# 32_-.net
KiCad netlist of a schematic drawn in Altium Designer
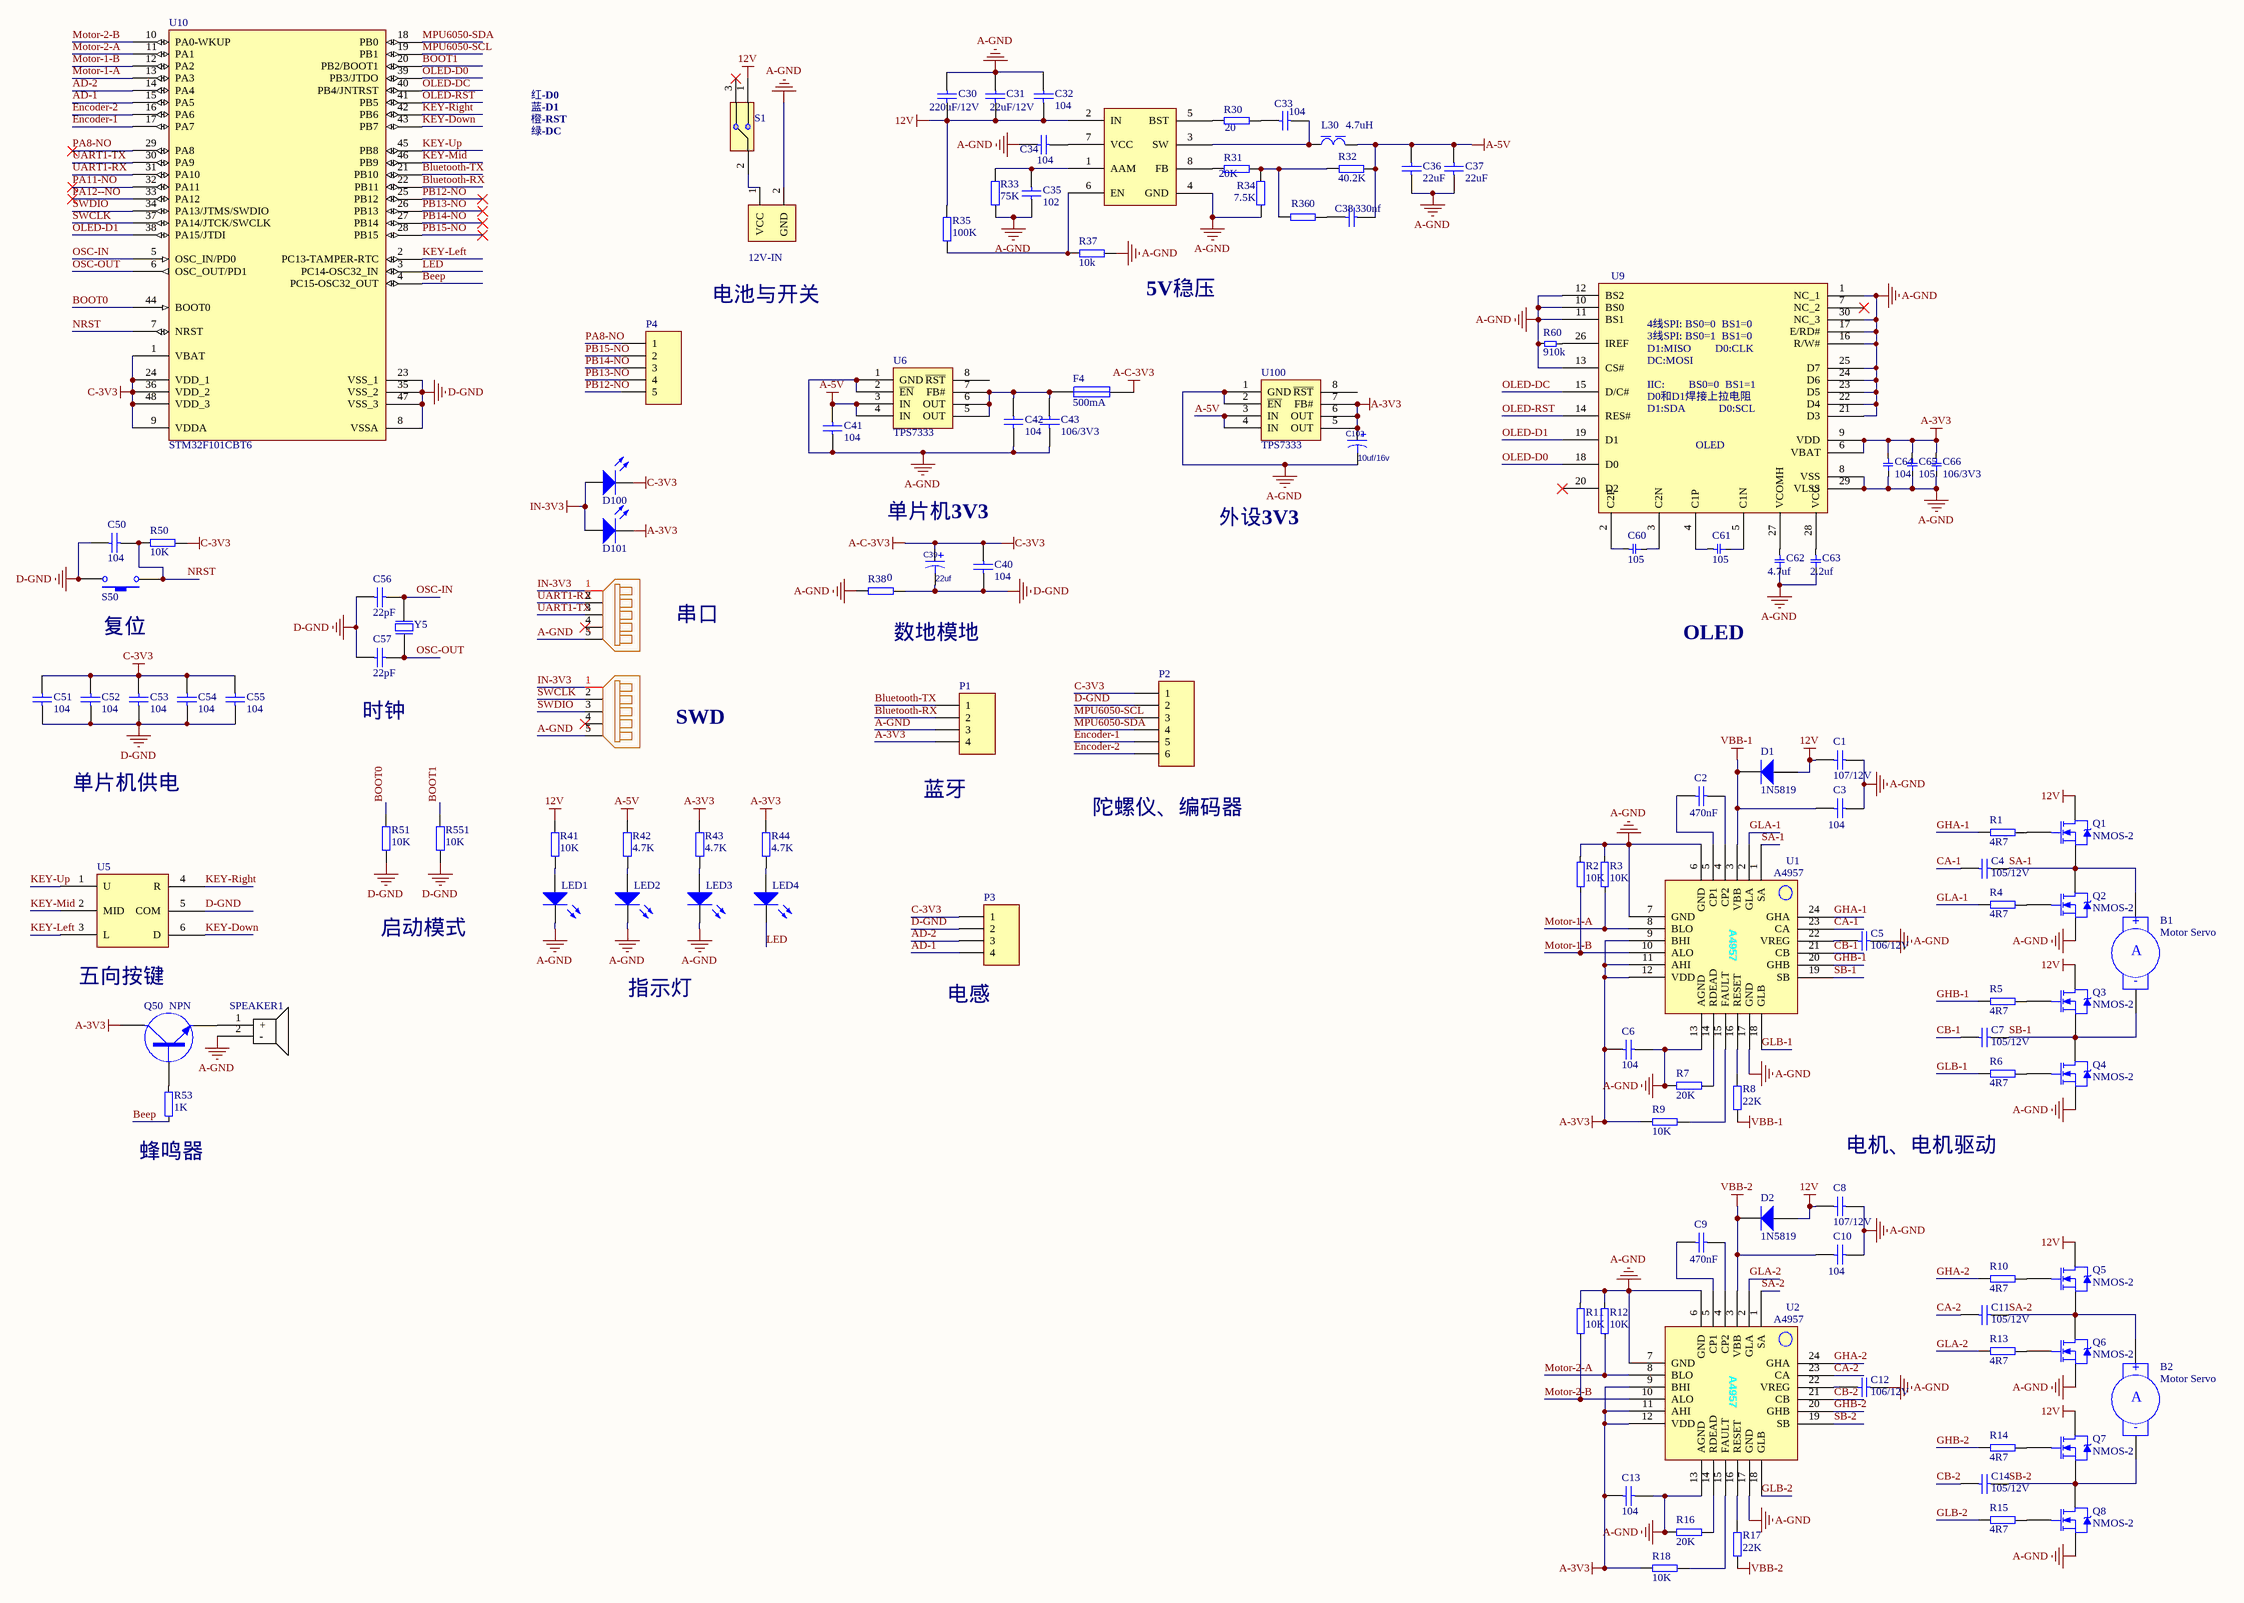
[diagram p0: 32直立车-原理图.SchDoc]

(export (version "E")
  (design (tool "Eeschema 10.0.6"))
  (components
    (comp (ref "12V-IN") (value "Power12") (footprint "VBAT-2") (libsource (lib "电磁第一版") (part "Power12")))
    (comp (ref "B1")
      (value "Motor Servo")
      (footprint "电机接口 - duplicate")
      (description "Servo Motor")
      (fields (field (name "PUBLISHER") "Altium Limited"))
      (libsource (lib "Miscellaneous Devices") (part "Motor Servo"))
    )
    (comp (ref "B2")
      (value "Motor Servo")
      (footprint "电机接口 - duplicate")
      (description "Servo Motor")
      (fields (field (name "PUBLISHER") "Altium Limited"))
      (libsource (lib "Miscellaneous Devices") (part "Motor Servo"))
    )
    (comp (ref "C1")
      (value "107/12V")
      (footprint "CAPC4532[1812]")
      (description "Chip Capacitor, Silkscreen Border")
      (fields
        (field (name "VOLTAGE") "63V")
        (field (name "TOLERANCE") "Y5V")
        (field (name "PUBLISHER") "Altium Limited")
      )
      (libsource (lib "!)Miscellaneous Integrated Library") (part "Cap Chip 2"))
    )
    (comp (ref "C2")
      (value "470nF")
      (footprint "CAPC1608[0603]")
      (description "Chip Capacitor, Silkscreen Border")
      (fields
        (field (name "VOLTAGE") "63V")
        (field (name "TOLERANCE") "Y5V")
        (field (name "PUBLISHER") "Altium Limited")
      )
      (libsource (lib "!)Miscellaneous Integrated Library") (part "Cap Chip 2"))
    )
    (comp (ref "C3")
      (value "104")
      (footprint "CAPC1608[0603]")
      (description "Chip Capacitor, Silkscreen Border")
      (fields
        (field (name "VOLTAGE") "63V")
        (field (name "TOLERANCE") "Y5V")
        (field (name "PUBLISHER") "Altium Limited")
      )
      (libsource (lib "!)Miscellaneous Integrated Library") (part "Cap Chip 2"))
    )
    (comp (ref "C4")
      (value "105/12V")
      (footprint "CAPC1608[0603]")
      (description "Chip Capacitor, Silkscreen Border")
      (fields
        (field (name "VOLTAGE") "63V")
        (field (name "TOLERANCE") "Y5V")
        (field (name "PUBLISHER") "Altium Limited")
      )
      (libsource (lib "!)Miscellaneous Integrated Library") (part "Cap Chip 2"))
    )
    (comp (ref "C5")
      (value "106/12V")
      (footprint "CAPC2012[0805]")
      (description "Chip Capacitor, Silkscreen Border")
      (fields
        (field (name "VOLTAGE") "63V")
        (field (name "TOLERANCE") "Y5V")
        (field (name "PUBLISHER") "Altium Limited")
      )
      (libsource (lib "!)Miscellaneous Integrated Library") (part "Cap Chip 2"))
    )
    (comp (ref "C6")
      (value "104")
      (footprint "CAPC1608[0603]")
      (description "Chip Capacitor, Silkscreen Border")
      (fields
        (field (name "VOLTAGE") "63V")
        (field (name "TOLERANCE") "Y5V")
        (field (name "PUBLISHER") "Altium Limited")
      )
      (libsource (lib "!)Miscellaneous Integrated Library") (part "Cap Chip 2"))
    )
    (comp (ref "C7")
      (value "105/12V")
      (footprint "CAPC1608[0603]")
      (description "Chip Capacitor, Silkscreen Border")
      (fields
        (field (name "VOLTAGE") "63V")
        (field (name "TOLERANCE") "Y5V")
        (field (name "PUBLISHER") "Altium Limited")
      )
      (libsource (lib "!)Miscellaneous Integrated Library") (part "Cap Chip 2"))
    )
    (comp (ref "C8")
      (value "107/12V")
      (footprint "CAPC4532[1812]")
      (description "Chip Capacitor, Silkscreen Border")
      (fields
        (field (name "VOLTAGE") "63V")
        (field (name "TOLERANCE") "Y5V")
        (field (name "PUBLISHER") "Altium Limited")
      )
      (libsource (lib "!)Miscellaneous Integrated Library") (part "Cap Chip 2"))
    )
    (comp (ref "C9")
      (value "470nF")
      (footprint "CAPC1608[0603]")
      (description "Chip Capacitor, Silkscreen Border")
      (fields
        (field (name "VOLTAGE") "63V")
        (field (name "TOLERANCE") "Y5V")
        (field (name "PUBLISHER") "Altium Limited")
      )
      (libsource (lib "!)Miscellaneous Integrated Library") (part "Cap Chip 2"))
    )
    (comp (ref "C10")
      (value "104")
      (footprint "CAPC1608[0603]")
      (description "Chip Capacitor, Silkscreen Border")
      (fields
        (field (name "VOLTAGE") "63V")
        (field (name "TOLERANCE") "Y5V")
        (field (name "PUBLISHER") "Altium Limited")
      )
      (libsource (lib "!)Miscellaneous Integrated Library") (part "Cap Chip 2"))
    )
    (comp (ref "C11")
      (value "105/12V")
      (footprint "CAPC1608[0603]")
      (description "Chip Capacitor, Silkscreen Border")
      (fields
        (field (name "VOLTAGE") "63V")
        (field (name "TOLERANCE") "Y5V")
        (field (name "PUBLISHER") "Altium Limited")
      )
      (libsource (lib "!)Miscellaneous Integrated Library") (part "Cap Chip 2"))
    )
    (comp (ref "C12")
      (value "106/12V")
      (footprint "CAPC2012[0805]")
      (description "Chip Capacitor, Silkscreen Border")
      (fields
        (field (name "VOLTAGE") "63V")
        (field (name "TOLERANCE") "Y5V")
        (field (name "PUBLISHER") "Altium Limited")
      )
      (libsource (lib "!)Miscellaneous Integrated Library") (part "Cap Chip 2"))
    )
    (comp (ref "C13")
      (value "104")
      (footprint "CAPC1608[0603]")
      (description "Chip Capacitor, Silkscreen Border")
      (fields
        (field (name "VOLTAGE") "63V")
        (field (name "TOLERANCE") "Y5V")
        (field (name "PUBLISHER") "Altium Limited")
      )
      (libsource (lib "!)Miscellaneous Integrated Library") (part "Cap Chip 2"))
    )
    (comp (ref "C14")
      (value "105/12V")
      (footprint "CAPC1608[0603]")
      (description "Chip Capacitor, Silkscreen Border")
      (fields
        (field (name "VOLTAGE") "63V")
        (field (name "TOLERANCE") "Y5V")
        (field (name "PUBLISHER") "Altium Limited")
      )
      (libsource (lib "!)Miscellaneous Integrated Library") (part "Cap Chip 2"))
    )
    (comp (ref "C30")
      (value "220uF/12V")
      (footprint "CAPT7343")
      (description "Chip Capacitor, PSpice Model")
      (fields (field (name "TOLERANCE") "Y5V") (field (name "PUBLISHER") "Altium Limited"))
      (libsource (lib "!)Miscellaneous Integrated Library") (part "Cap Chip 1"))
    )
    (comp (ref "C31")
      (value "22uF/12V")
      (footprint "CAPC2012[0805]")
      (description "Chip Capacitor, PSpice Model")
      (fields
        (field (name "TOLERANCE") "Y5V")
        (field (name "VOLTAGE") "63V")
        (field (name "PUBLISHER") "Altium Limited")
      )
      (libsource (lib "!)Miscellaneous Integrated Library") (part "Cap Chip 1"))
    )
    (comp (ref "C32")
      (value "104")
      (footprint "CAPC1608[0603]")
      (description "Chip Capacitor, PSpice Model")
      (fields
        (field (name "TOLERANCE") "Y5V")
        (field (name "VOLTAGE") "63V")
        (field (name "PUBLISHER") "Altium Limited")
      )
      (libsource (lib "!)Miscellaneous Integrated Library") (part "Cap Chip 1"))
    )
    (comp (ref "C33")
      (value "104")
      (footprint "CAPC1608[0603]")
      (description "Chip Capacitor, PSpice Model")
      (fields
        (field (name "TOLERANCE") "Y5V")
        (field (name "VOLTAGE") "63V")
        (field (name "PUBLISHER") "Altium Limited")
      )
      (libsource (lib "!)Miscellaneous Integrated Library") (part "Cap Chip 1"))
    )
    (comp (ref "C34")
      (value "104")
      (footprint "CAPC1608[0603]")
      (description "Chip Capacitor, PSpice Model")
      (fields
        (field (name "TOLERANCE") "Y5V")
        (field (name "VOLTAGE") "63V")
        (field (name "PUBLISHER") "Altium Limited")
      )
      (libsource (lib "!)Miscellaneous Integrated Library") (part "Cap Chip 1"))
    )
    (comp (ref "C35")
      (value "102")
      (footprint "CAPC1608[0603]")
      (description "Chip Capacitor, PSpice Model")
      (fields
        (field (name "TOLERANCE") "Y5V")
        (field (name "VOLTAGE") "63V")
        (field (name "PUBLISHER") "Altium Limited")
      )
      (libsource (lib "!)Miscellaneous Integrated Library") (part "Cap Chip 1"))
    )
    (comp (ref "C36")
      (value "22uF")
      (footprint "CAPC2012[0805]")
      (description "Chip Capacitor, PSpice Model")
      (fields
        (field (name "TOLERANCE") "Y5V")
        (field (name "VOLTAGE") "63V")
        (field (name "PUBLISHER") "Altium Limited")
      )
      (libsource (lib "!)Miscellaneous Integrated Library") (part "Cap Chip 1"))
    )
    (comp (ref "C37")
      (value "22uF")
      (footprint "CAPC2012[0805]")
      (description "Chip Capacitor, PSpice Model")
      (fields
        (field (name "TOLERANCE") "Y5V")
        (field (name "VOLTAGE") "63V")
        (field (name "PUBLISHER") "Altium Limited")
      )
      (libsource (lib "!)Miscellaneous Integrated Library") (part "Cap Chip 1"))
    )
    (comp (ref "C38")
      (value "330nf")
      (footprint "CAPC1608[0603]")
      (description "Chip Capacitor, PSpice Model")
      (fields
        (field (name "TOLERANCE") "Y5V")
        (field (name "VOLTAGE") "63V")
        (field (name "PUBLISHER") "Altium Limited")
      )
      (libsource (lib "!)Miscellaneous Integrated Library") (part "Cap Chip 1"))
    )
    (comp (ref "C39")
      (value "22uf")
      (footprint "CAPT7343")
      (description "Polarized Capacitor (Axial)")
      (fields (field (name "Comment") "Cap Pol2") (field (name "PUBLISHER") "Altium Limited"))
      (libsource (lib "TheCar") (part "Cap Pol2"))
    )
    (comp (ref "C40")
      (value "104")
      (footprint "CAPC1608[0603]")
      (description "Chip Capacitor, PSpice Model")
      (fields
        (field (name "TOLERANCE") "Y5V")
        (field (name "VOLTAGE") "63V")
        (field (name "PUBLISHER") "Altium Limited")
      )
      (libsource (lib "!)Miscellaneous Integrated Library") (part "Cap Chip 1"))
    )
    (comp (ref "C41")
      (value "104")
      (footprint "CAPC1608[0603]")
      (description "Chip Capacitor, Silkscreen Border")
      (fields
        (field (name "VOLTAGE") "63V")
        (field (name "TOLERANCE") "Y5V")
        (field (name "PUBLISHER") "Altium Limited")
      )
      (libsource (lib "!)Miscellaneous Integrated Library") (part "Cap Chip 2"))
    )
    (comp (ref "C42")
      (value "104")
      (footprint "CAPC1608[0603]")
      (description "Chip Capacitor, Silkscreen Border")
      (fields
        (field (name "VOLTAGE") "63V")
        (field (name "TOLERANCE") "Y5V")
        (field (name "PUBLISHER") "Altium Limited")
      )
      (libsource (lib "!)Miscellaneous Integrated Library") (part "Cap Chip 2"))
    )
    (comp (ref "C43")
      (value "106/3V3")
      (footprint "CAPC1608[0603]")
      (description "Chip Capacitor, Silkscreen Border")
      (fields
        (field (name "VOLTAGE") "63V")
        (field (name "TOLERANCE") "Y5V")
        (field (name "PUBLISHER") "Altium Limited")
      )
      (libsource (lib "!)Miscellaneous Integrated Library") (part "Cap Chip 2"))
    )
    (comp (ref "C50")
      (value "104")
      (footprint "CAPC1608[0603]")
      (description "Chip Capacitor, Silkscreen Border")
      (fields
        (field (name "VOLTAGE") "63V")
        (field (name "TOLERANCE") "Y5V")
        (field (name "PUBLISHER") "Altium Limited")
      )
      (libsource (lib "!)Miscellaneous Integrated Library") (part "Cap Chip 2"))
    )
    (comp (ref "C51")
      (value "104")
      (footprint "CAPC1608[0603]")
      (description "Chip Capacitor, Silkscreen Border")
      (fields
        (field (name "VOLTAGE") "63V")
        (field (name "TOLERANCE") "Y5V")
        (field (name "PUBLISHER") "Altium Limited")
      )
      (libsource (lib "!)Miscellaneous Integrated Library") (part "Cap Chip 2"))
    )
    (comp (ref "C52")
      (value "104")
      (footprint "CAPC1608[0603]")
      (description "Chip Capacitor, Silkscreen Border")
      (fields
        (field (name "VOLTAGE") "63V")
        (field (name "TOLERANCE") "Y5V")
        (field (name "PUBLISHER") "Altium Limited")
      )
      (libsource (lib "!)Miscellaneous Integrated Library") (part "Cap Chip 2"))
    )
    (comp (ref "C53")
      (value "104")
      (footprint "CAPC1608[0603]")
      (description "Chip Capacitor, Silkscreen Border")
      (fields
        (field (name "VOLTAGE") "63V")
        (field (name "TOLERANCE") "Y5V")
        (field (name "PUBLISHER") "Altium Limited")
      )
      (libsource (lib "!)Miscellaneous Integrated Library") (part "Cap Chip 2"))
    )
    (comp (ref "C54")
      (value "104")
      (footprint "CAPC1608[0603]")
      (description "Chip Capacitor, Silkscreen Border")
      (fields
        (field (name "VOLTAGE") "63V")
        (field (name "TOLERANCE") "Y5V")
        (field (name "PUBLISHER") "Altium Limited")
      )
      (libsource (lib "!)Miscellaneous Integrated Library") (part "Cap Chip 2"))
    )
    (comp (ref "C55")
      (value "104")
      (footprint "CAPC1608[0603]")
      (description "Chip Capacitor, Silkscreen Border")
      (fields
        (field (name "VOLTAGE") "63V")
        (field (name "TOLERANCE") "Y5V")
        (field (name "PUBLISHER") "Altium Limited")
      )
      (libsource (lib "!)Miscellaneous Integrated Library") (part "Cap Chip 2"))
    )
    (comp (ref "C56")
      (value "22pF")
      (footprint "CAPC1608[0603]")
      (description "Chip Capacitor, Silkscreen Border")
      (fields
        (field (name "VOLTAGE") "63V")
        (field (name "TOLERANCE") "Y5V")
        (field (name "PUBLISHER") "Altium Limited")
      )
      (libsource (lib "!)Miscellaneous Integrated Library") (part "Cap Chip 2"))
    )
    (comp (ref "C57")
      (value "22pF")
      (footprint "CAPC1608[0603]")
      (description "Chip Capacitor, Silkscreen Border")
      (fields
        (field (name "VOLTAGE") "63V")
        (field (name "TOLERANCE") "Y5V")
        (field (name "PUBLISHER") "Altium Limited")
      )
      (libsource (lib "!)Miscellaneous Integrated Library") (part "Cap Chip 2"))
    )
    (comp (ref "C60") (value "105") (footprint "CAPC1608[0603]") (libsource (lib "电容") (part "ECAP")))
    (comp (ref "C61") (value "105") (footprint "CAPC1608[0603]") (libsource (lib "电容") (part "ECAP")))
    (comp (ref "C62") (value "4.7uf") (footprint "CAPC2012[0805]") (libsource (lib "电容") (part "ECAP")))
    (comp (ref "C63") (value "2.2uf") (footprint "CAPC1608[0603]") (libsource (lib "电容") (part "ECAP")))
    (comp (ref "C64") (value "104") (footprint "CAPC1608[0603]") (libsource (lib "电容") (part "ECAP")))
    (comp (ref "C65") (value "105") (footprint "CAPC1608[0603]") (libsource (lib "电容") (part "ECAP")))
    (comp (ref "C66") (value "106/3V3") (footprint "CAPC2012[0805]") (libsource (lib "电容") (part "ECAP")))
    (comp (ref "C102")
      (value "10uf/16v")
      (footprint "钽电容3216")
      (description "Polarized Capacitor (Axial)")
      (fields (field (name "Comment") "Cap Pol2") (field (name "PUBLISHER") "Altium Limited"))
      (libsource (lib "TheCar") (part "Cap Pol2"))
    )
    (comp (ref "D1")
      (value "1N5819")
      (footprint "SMA[DO-214AC]")
      (description "Default Diode")
      (fields (field (name "PUBLISHER") "Altium Limited"))
      (libsource (lib "Miscellaneous Devices") (part "Diode"))
    )
    (comp (ref "D2")
      (value "1N5819")
      (footprint "SMA[DO-214AC]")
      (description "Default Diode")
      (fields (field (name "PUBLISHER") "Altium Limited"))
      (libsource (lib "Miscellaneous Devices") (part "Diode"))
    )
    (comp (ref "D100")
      (value "Red")
      (footprint "LED-0603")
      (description "Typical Chip LED")
      (fields (field (name "PUBLISHER") "Altium Limited"))
      (libsource (lib "!)Miscellaneous Integrated Library") (part "LED Chip"))
    )
    (comp (ref "D101")
      (value "Red")
      (footprint "LED-0603")
      (description "Typical Chip LED")
      (fields (field (name "PUBLISHER") "Altium Limited"))
      (libsource (lib "!)Miscellaneous Integrated Library") (part "LED Chip"))
    )
    (comp (ref "F4")
      (value "500mA")
      (footprint "CAPC2012[0805]")
      (description "Fuse")
      (fields (field (name "PUBLISHER") "Altium Limited"))
      (libsource (lib "主板 v2.0 最小系统") (part "Fuse chip"))
    )
    (comp (ref "L30")
      (value "4.7uH")
      (footprint "CD52")
      (description "Power Inductor, Ferrite-Core")
      (fields (field (name "PUBLISHER") "Altium Limited"))
      (libsource (lib "!)Miscellaneous Integrated Library") (part "Ind Power"))
    )
    (comp (ref "LED1")
      (value "Red")
      (footprint "LEDC1608(0603)")
      (description "Typical Chip LED")
      (fields (field (name "PUBLISHER") "Altium Limited"))
      (libsource (lib "") (part "LED Chip_1"))
    )
    (comp (ref "LED2")
      (value "Red")
      (footprint "LEDC1608(0603)")
      (description "Typical Chip LED")
      (fields (field (name "PUBLISHER") "Altium Limited"))
      (libsource (lib "") (part "LED Chip_1"))
    )
    (comp (ref "LED3")
      (value "Red")
      (footprint "LEDC1608(0603)")
      (description "Typical Chip LED")
      (fields (field (name "PUBLISHER") "Altium Limited"))
      (libsource (lib "") (part "LED Chip_1"))
    )
    (comp (ref "LED4")
      (value "Red")
      (footprint "LEDC1608(0603)")
      (description "Typical Chip LED")
      (fields (field (name "PUBLISHER") "Altium Limited"))
      (libsource (lib "") (part "LED Chip_1"))
    )
    (comp (ref "P1")
      (value "~")
      (footprint "MK1.25_4P立")
      (description "Header, 4-Pin")
      (fields (field (name "PUBLISHER") "Altium Limited"))
      (libsource (lib "!)Miscellaneous Integrated Library") (part "Header 4"))
    )
    (comp (ref "P2")
      (value "陀螺仪、编码器")
      (footprint "6P-卧头")
      (description "Header, 6-Pin")
      (fields (field (name "PUBLISHER") "Altium Limited"))
      (libsource (lib "!)Miscellaneous Integrated Library") (part "Header 6"))
    )
    (comp (ref "P3")
      (value "~")
      (footprint "MK1.25_4P立")
      (description "Header, 4-Pin")
      (fields (field (name "PUBLISHER") "Altium Limited"))
      (libsource (lib "!)Miscellaneous Integrated Library") (part "Header 4"))
    )
    (comp (ref "P4")
      (value "Header 5")
      (footprint "扩展口-5P")
      (description "Header, 5-Pin")
      (fields (field (name "PUBLISHER") "Altium Limited"))
      (libsource (lib "!)Miscellaneous Integrated Library") (part "Header 5"))
    )
    (comp (ref "Q1")
      (value "NMOS-2")
      (footprint "IR7843-mg")
      (description "N-Channel Power MOSFET")
      (fields (field (name "PUBLISHER") "Altium Limited"))
      (libsource (lib "Miscellaneous Devices") (part "NMOS-2"))
    )
    (comp (ref "Q2")
      (value "NMOS-2")
      (footprint "IR7843-mg")
      (description "N-Channel Power MOSFET")
      (fields (field (name "PUBLISHER") "Altium Limited"))
      (libsource (lib "Miscellaneous Devices") (part "NMOS-2"))
    )
    (comp (ref "Q3")
      (value "NMOS-2")
      (footprint "IR7843-mg")
      (description "N-Channel Power MOSFET")
      (fields (field (name "PUBLISHER") "Altium Limited"))
      (libsource (lib "Miscellaneous Devices") (part "NMOS-2"))
    )
    (comp (ref "Q4")
      (value "NMOS-2")
      (footprint "IR7843-mg")
      (description "N-Channel Power MOSFET")
      (fields (field (name "PUBLISHER") "Altium Limited"))
      (libsource (lib "Miscellaneous Devices") (part "NMOS-2"))
    )
    (comp (ref "Q5")
      (value "NMOS-2")
      (footprint "IR7843-mg")
      (description "N-Channel Power MOSFET")
      (fields (field (name "PUBLISHER") "Altium Limited"))
      (libsource (lib "Miscellaneous Devices") (part "NMOS-2"))
    )
    (comp (ref "Q6")
      (value "NMOS-2")
      (footprint "IR7843-mg")
      (description "N-Channel Power MOSFET")
      (fields (field (name "PUBLISHER") "Altium Limited"))
      (libsource (lib "Miscellaneous Devices") (part "NMOS-2"))
    )
    (comp (ref "Q7")
      (value "NMOS-2")
      (footprint "IR7843-mg")
      (description "N-Channel Power MOSFET")
      (fields (field (name "PUBLISHER") "Altium Limited"))
      (libsource (lib "Miscellaneous Devices") (part "NMOS-2"))
    )
    (comp (ref "Q8")
      (value "NMOS-2")
      (footprint "IR7843-mg")
      (description "N-Channel Power MOSFET")
      (fields (field (name "PUBLISHER") "Altium Limited"))
      (libsource (lib "Miscellaneous Devices") (part "NMOS-2"))
    )
    (comp (ref "Q50")
      (value "NPN")
      (footprint "SOT23")
      (description "NPN Transistor")
      (libsource (lib "杂元件库") (part "NPN"))
    )
    (comp (ref "R1")
      (value "4R7")
      (footprint "RESC1608[0603]")
      (description "Chip Resistor, Border Silkscreen On PCB Library")
      (fields (field (name "TOLERANCE") "5%") (field (name "PUBLISHER") "Altium Limited"))
      (libsource (lib "!)Miscellaneous Integrated Library") (part "Res Chip 2p 2"))
    )
    (comp (ref "R2")
      (value "10K")
      (footprint "RESC1608[0603]")
      (description "resistor")
      (libsource (lib "常用原理图.~(18)") (part "R-10K"))
    )
    (comp (ref "R3")
      (value "10K")
      (footprint "RESC1608[0603]")
      (description "resistor")
      (libsource (lib "常用原理图.~(18)") (part "R-10K"))
    )
    (comp (ref "R4")
      (value "4R7")
      (footprint "RESC1608[0603]")
      (description "Chip Resistor, Border Silkscreen On PCB Library")
      (fields (field (name "TOLERANCE") "5%") (field (name "PUBLISHER") "Altium Limited"))
      (libsource (lib "!)Miscellaneous Integrated Library") (part "Res Chip 2p 2"))
    )
    (comp (ref "R5")
      (value "4R7")
      (footprint "RESC1608[0603]")
      (description "Chip Resistor, Border Silkscreen On PCB Library")
      (fields (field (name "TOLERANCE") "5%") (field (name "PUBLISHER") "Altium Limited"))
      (libsource (lib "!)Miscellaneous Integrated Library") (part "Res Chip 2p 2"))
    )
    (comp (ref "R6")
      (value "4R7")
      (footprint "RESC1608[0603]")
      (description "Chip Resistor, Border Silkscreen On PCB Library")
      (fields (field (name "TOLERANCE") "5%") (field (name "PUBLISHER") "Altium Limited"))
      (libsource (lib "!)Miscellaneous Integrated Library") (part "Res Chip 2p 2"))
    )
    (comp (ref "R7")
      (value "20K")
      (footprint "RESC1608[0603]")
      (description "Chip Resistor, Border Silkscreen On PCB Library")
      (fields (field (name "TOLERANCE") "5%") (field (name "PUBLISHER") "Altium Limited"))
      (libsource (lib "!)Miscellaneous Integrated Library") (part "Res Chip 2p 2"))
    )
    (comp (ref "R8")
      (value "22K")
      (footprint "RESC1608[0603]")
      (description "Chip Resistor, Border Silkscreen On PCB Library")
      (fields (field (name "TOLERANCE") "5%") (field (name "PUBLISHER") "Altium Limited"))
      (libsource (lib "!)Miscellaneous Integrated Library") (part "Res Chip 2p 2"))
    )
    (comp (ref "R9")
      (value "10K")
      (footprint "RESC1608[0603]")
      (description "Chip Resistor, Border Silkscreen On PCB Library")
      (fields (field (name "TOLERANCE") "5%") (field (name "PUBLISHER") "Altium Limited"))
      (libsource (lib "!)Miscellaneous Integrated Library") (part "Res Chip 2p 2"))
    )
    (comp (ref "R10")
      (value "4R7")
      (footprint "RESC1608[0603]")
      (description "Chip Resistor, Border Silkscreen On PCB Library")
      (fields (field (name "TOLERANCE") "5%") (field (name "PUBLISHER") "Altium Limited"))
      (libsource (lib "!)Miscellaneous Integrated Library") (part "Res Chip 2p 2"))
    )
    (comp (ref "R11")
      (value "10K")
      (footprint "RESC1608[0603]")
      (description "resistor")
      (libsource (lib "常用原理图.~(18)") (part "R-10K"))
    )
    (comp (ref "R12")
      (value "10K")
      (footprint "RESC1608[0603]")
      (description "resistor")
      (libsource (lib "常用原理图.~(18)") (part "R-10K"))
    )
    (comp (ref "R13")
      (value "4R7")
      (footprint "RESC1608[0603]")
      (description "Chip Resistor, Border Silkscreen On PCB Library")
      (fields (field (name "TOLERANCE") "5%") (field (name "PUBLISHER") "Altium Limited"))
      (libsource (lib "!)Miscellaneous Integrated Library") (part "Res Chip 2p 2"))
    )
    (comp (ref "R14")
      (value "4R7")
      (footprint "RESC1608[0603]")
      (description "Chip Resistor, Border Silkscreen On PCB Library")
      (fields (field (name "TOLERANCE") "5%") (field (name "PUBLISHER") "Altium Limited"))
      (libsource (lib "!)Miscellaneous Integrated Library") (part "Res Chip 2p 2"))
    )
    (comp (ref "R15")
      (value "4R7")
      (footprint "RESC1608[0603]")
      (description "Chip Resistor, Border Silkscreen On PCB Library")
      (fields (field (name "TOLERANCE") "5%") (field (name "PUBLISHER") "Altium Limited"))
      (libsource (lib "!)Miscellaneous Integrated Library") (part "Res Chip 2p 2"))
    )
    (comp (ref "R16")
      (value "20K")
      (footprint "RESC1608[0603]")
      (description "Chip Resistor, Border Silkscreen On PCB Library")
      (fields (field (name "TOLERANCE") "5%") (field (name "PUBLISHER") "Altium Limited"))
      (libsource (lib "!)Miscellaneous Integrated Library") (part "Res Chip 2p 2"))
    )
    (comp (ref "R17")
      (value "22K")
      (footprint "RESC1608[0603]")
      (description "Chip Resistor, Border Silkscreen On PCB Library")
      (fields (field (name "TOLERANCE") "5%") (field (name "PUBLISHER") "Altium Limited"))
      (libsource (lib "!)Miscellaneous Integrated Library") (part "Res Chip 2p 2"))
    )
    (comp (ref "R18")
      (value "10K")
      (footprint "RESC1608[0603]")
      (description "Chip Resistor, Border Silkscreen On PCB Library")
      (fields (field (name "TOLERANCE") "5%") (field (name "PUBLISHER") "Altium Limited"))
      (libsource (lib "!)Miscellaneous Integrated Library") (part "Res Chip 2p 2"))
    )
    (comp (ref "R30")
      (value "20")
      (footprint "RESC1608[0603]")
      (description "Chip Resistor, PSpice Model, IPC PCB Library Drawing")
      (fields (field (name "TOLERANCE") "5%") (field (name "PUBLISHER") "Altium Limited"))
      (libsource (lib "!)Miscellaneous Integrated Library") (part "Res Chip 2p 1"))
    )
    (comp (ref "R31")
      (value "20K")
      (footprint "RESC1608[0603]")
      (description "Chip Resistor, PSpice Model, IPC PCB Library Drawing")
      (fields (field (name "TOLERANCE") "5%") (field (name "PUBLISHER") "Altium Limited"))
      (libsource (lib "!)Miscellaneous Integrated Library") (part "Res Chip 2p 1"))
    )
    (comp (ref "R32")
      (value "40.2K")
      (footprint "RESC1608[0603]")
      (description "Chip Resistor, PSpice Model, IPC PCB Library Drawing")
      (fields (field (name "TOLERANCE") "5%") (field (name "PUBLISHER") "Altium Limited"))
      (libsource (lib "!)Miscellaneous Integrated Library") (part "Res Chip 2p 1"))
    )
    (comp (ref "R33")
      (value "75K")
      (footprint "RESC1608[0603]")
      (description "Chip Resistor, PSpice Model, IPC PCB Library Drawing")
      (fields (field (name "TOLERANCE") "5%") (field (name "PUBLISHER") "Altium Limited"))
      (libsource (lib "!)Miscellaneous Integrated Library") (part "Res Chip 2p 1"))
    )
    (comp (ref "R34")
      (value "7.5K")
      (footprint "RESC1608[0603]")
      (description "Chip Resistor, PSpice Model, IPC PCB Library Drawing")
      (fields (field (name "TOLERANCE") "5%") (field (name "PUBLISHER") "Altium Limited"))
      (libsource (lib "!)Miscellaneous Integrated Library") (part "Res Chip 2p 1"))
    )
    (comp (ref "R35")
      (value "100K")
      (footprint "RESC1608[0603]")
      (description "Chip Resistor, PSpice Model, IPC PCB Library Drawing")
      (fields (field (name "TOLERANCE") "5%") (field (name "PUBLISHER") "Altium Limited"))
      (libsource (lib "!)Miscellaneous Integrated Library") (part "Res Chip 2p 1"))
    )
    (comp (ref "R36")
      (value "0")
      (footprint "RESC1608[0603]")
      (description "Chip Resistor, PSpice Model, IPC PCB Library Drawing")
      (fields (field (name "TOLERANCE") "5%") (field (name "PUBLISHER") "Altium Limited"))
      (libsource (lib "!)Miscellaneous Integrated Library") (part "Res Chip 2p 1"))
    )
    (comp (ref "R37")
      (value "10k")
      (footprint "RESC1608[0603]")
      (description "Chip Resistor, PSpice Model, IPC PCB Library Drawing")
      (fields (field (name "TOLERANCE") "5%") (field (name "PUBLISHER") "Altium Limited"))
      (libsource (lib "!)Miscellaneous Integrated Library") (part "Res Chip 2p 1"))
    )
    (comp (ref "R38")
      (value "0")
      (footprint "RESC1608[0603]")
      (description "Chip Resistor, PSpice Model, IPC PCB Library Drawing")
      (fields (field (name "TOLERANCE") "5%") (field (name "PUBLISHER") "Altium Limited"))
      (libsource (lib "!)Miscellaneous Integrated Library") (part "Res Chip 2p 1"))
    )
    (comp (ref "R41")
      (value "10K")
      (footprint "RESC1608[0603]")
      (description "Chip Resistor, PSpice Model, IPC PCB Library Drawing")
      (fields (field (name "TOLERANCE") "5%") (field (name "PUBLISHER") "Altium Limited"))
      (libsource (lib "!)Miscellaneous Integrated Library") (part "Res Chip 2p 1"))
    )
    (comp (ref "R42")
      (value "4.7K")
      (footprint "RESC1608[0603]")
      (description "Chip Resistor, PSpice Model, IPC PCB Library Drawing")
      (fields (field (name "TOLERANCE") "5%") (field (name "PUBLISHER") "Altium Limited"))
      (libsource (lib "!)Miscellaneous Integrated Library") (part "Res Chip 2p 1"))
    )
    (comp (ref "R43")
      (value "4.7K")
      (footprint "RESC1608[0603]")
      (description "Chip Resistor, PSpice Model, IPC PCB Library Drawing")
      (fields (field (name "TOLERANCE") "5%") (field (name "PUBLISHER") "Altium Limited"))
      (libsource (lib "!)Miscellaneous Integrated Library") (part "Res Chip 2p 1"))
    )
    (comp (ref "R44")
      (value "4.7K")
      (footprint "RESC1608[0603]")
      (description "Chip Resistor, PSpice Model, IPC PCB Library Drawing")
      (fields (field (name "TOLERANCE") "5%") (field (name "PUBLISHER") "Altium Limited"))
      (libsource (lib "!)Miscellaneous Integrated Library") (part "Res Chip 2p 1"))
    )
    (comp (ref "R50")
      (value "10K")
      (footprint "RESC1608[0603]")
      (description "Chip Resistor, PSpice Model, IPC PCB Library Drawing")
      (fields (field (name "TOLERANCE") "5%") (field (name "PUBLISHER") "Altium Limited"))
      (libsource (lib "!)Miscellaneous Integrated Library") (part "Res Chip 2p 1"))
    )
    (comp (ref "R51")
      (value "10K")
      (footprint "RESC1608[0603]")
      (description "Chip Resistor, PSpice Model, IPC PCB Library Drawing")
      (fields (field (name "TOLERANCE") "5%") (field (name "PUBLISHER") "Altium Limited"))
      (libsource (lib "!)Miscellaneous Integrated Library") (part "Res Chip 2p 1"))
    )
    (comp (ref "R53") (value "1K") (footprint "RESC1608[0603]") (libsource (lib "电阻") (part "RES")))
    (comp (ref "R60")
      (value "910k")
      (footprint "RESC1608[0603]")
      (description "CR85-102J")
      (libsource (lib "常用原理图") (part "1K"))
    )
    (comp (ref "R551")
      (value "10K")
      (footprint "RESC1608[0603]")
      (description "Chip Resistor, PSpice Model, IPC PCB Library Drawing")
      (fields (field (name "TOLERANCE") "5%") (field (name "PUBLISHER") "Altium Limited"))
      (libsource (lib "!)Miscellaneous Integrated Library") (part "Res Chip 2p 1"))
    )
    (comp (ref "S1") (value "switch") (footprint "2(-1)脚3A开关-立") (libsource (lib "电磁第一版") (part "switch")))
    (comp (ref "S50")
      (value "SW-PB")
      (footprint "key3*4*2")
      (description "Switch")
      (fields (field (name "PUBLISHER") "Altium Limited"))
      (libsource (lib "!)Miscellaneous Integrated Library") (part "SW-PB"))
    )
    (comp (ref "SPEAKER1") (value "有源蜂鸣器") (footprint "小Beep") (libsource (lib "蜂鸣器") (part "有源蜂鸣器")))
    (comp (ref "U1")
      (value "A4957")
      (footprint "QFN-24")
      (description "A4957SESTR-T")
      (libsource (lib "A4957 Dual Motor Driver V1.0") (part "A4957"))
    )
    (comp (ref "U2")
      (value "A4957")
      (footprint "QFN-24")
      (description "A4957SESTR-T")
      (libsource (lib "A4957 Dual Motor Driver V1.0") (part "A4957"))
    )
    (comp (ref "U5") (value "五向按键") (footprint "5向key-小") (libsource (lib "没有的器件原理图") (part "五向按键")))
    (comp (ref "U6") (value "TPS7333") (footprint "SOIC8") (libsource (lib "库") (part "TPS73xx")))
    (comp (ref "U9") (value "oled") (footprint "oled") (libsource (lib "电磁第一版") (part "OLED_1306")))
    (comp (ref "U10")
      (value "STM32F101CBT6")
      (footprint "LQFP48_N")
      (description "STM32 ARM-based 32-bit MCU with 128 Kbytes Flash, 48-pin LQFP, Industrial Temperature")
      (fields (field (name "PUBLISHER") "Altium Limited"))
      (libsource (lib "ST Microcontroller 32-Bit STM32") (part "STM32F101CBT6"))
    )
    (comp (ref "U30") (value "MP2315") (footprint "MP2315用SOP8") (libsource (lib "相关原理图封装") (part "MP2315")))
    (comp (ref "U100") (value "TPS7333") (footprint "SOIC8") (libsource (lib "库") (part "TPS73xx")))
    (comp (ref "USB1")
      (value "USB-5P")
      (footprint "Micro USB 牛角")
      (description "USB CONNECTOR")
      (libsource (lib "!)Miscellaneous Integrated Library") (part "USB-5P"))
    )
    (comp (ref "USB2")
      (value "USB-5P")
      (footprint "Micro USB 牛角")
      (description "USB CONNECTOR")
      (libsource (lib "!)Miscellaneous Integrated Library") (part "USB-5P"))
    )
    (comp (ref "Y5")
      (value "~")
      (footprint "4脚晶振-5032")
      (description "Crystal Oscillator")
      (fields (field (name "PUBLISHER") "Altium Limited"))
      (libsource (lib "!)Miscellaneous Integrated Library") (part "XTAL"))
    )
  )
  (nets
    (net (code "2") (name "/AD-1") (class "Default")
      (node (ref "P3") (pin "4") (pinfunction "4_4") (pintype "passive"))
      (node (ref "U10") (pin "15") (pinfunction "PA5_15") (pintype "bidirectional"))
    )
    (net (code "3") (name "/AD-2") (class "Default")
      (node (ref "P3") (pin "3") (pinfunction "3_3") (pintype "passive"))
      (node (ref "U10") (pin "14") (pinfunction "PA4_14") (pintype "bidirectional"))
    )
    (net (code "4") (name "/BOOT0") (class "Default")
      (node (ref "R51") (pin "2") (pinfunction "2_2") (pintype "passive"))
      (node (ref "U10") (pin "44") (pinfunction "BOOT0_44") (pintype "input"))
    )
    (net (code "5") (name "/BOOT1") (class "Default")
      (node (ref "R551") (pin "2") (pinfunction "2_2") (pintype "passive"))
      (node (ref "U10") (pin "20") (pinfunction "PB2/BOOT1_20") (pintype "bidirectional"))
    )
    (net (code "6") (name "/Beep") (class "Default")
      (node (ref "R53") (pin "1") (pinfunction "1_1") (pintype "passive"))
      (node (ref "U10") (pin "4") (pinfunction "PC15-OSC32_OUT_4") (pintype "bidirectional"))
    )
    (net (code "7") (name "/Bluetooth-RX") (class "Default")
      (node (ref "P1") (pin "2") (pinfunction "2_2") (pintype "passive"))
      (node (ref "U10") (pin "22") (pinfunction "PB11_22") (pintype "bidirectional"))
    )
    (net (code "8") (name "/Bluetooth-TX") (class "Default")
      (node (ref "P1") (pin "1") (pinfunction "1_1") (pintype "passive"))
      (node (ref "U10") (pin "21") (pinfunction "PB10_21") (pintype "bidirectional"))
    )
    (net (code "9") (name "/CA-1") (class "Default")
      (node (ref "C4") (pin "1") (pinfunction "1_1") (pintype "passive"))
      (node (ref "U1") (pin "23") (pinfunction "CA_23") (pintype "passive"))
    )
    (net (code "10") (name "/CA-2") (class "Default")
      (node (ref "C11") (pin "1") (pinfunction "1_1") (pintype "passive"))
      (node (ref "U2") (pin "23") (pinfunction "CA_23") (pintype "passive"))
    )
    (net (code "11") (name "/CB-1") (class "Default")
      (node (ref "C7") (pin "1") (pinfunction "1_1") (pintype "passive"))
      (node (ref "U1") (pin "21") (pinfunction "CB_21") (pintype "passive"))
    )
    (net (code "12") (name "/CB-2") (class "Default")
      (node (ref "C14") (pin "1") (pinfunction "1_1") (pintype "passive"))
      (node (ref "U2") (pin "21") (pinfunction "CB_21") (pintype "passive"))
    )
    (net (code "13") (name "/Encoder-1") (class "Default")
      (node (ref "P2") (pin "5") (pinfunction "5_5") (pintype "passive"))
      (node (ref "U10") (pin "17") (pinfunction "PA7_17") (pintype "bidirectional"))
    )
    (net (code "14") (name "/Encoder-2") (class "Default")
      (node (ref "P2") (pin "6") (pinfunction "6_6") (pintype "passive"))
      (node (ref "U10") (pin "16") (pinfunction "PA6_16") (pintype "bidirectional"))
    )
    (net (code "15") (name "/GHA-1") (class "Default")
      (node (ref "R1") (pin "2") (pinfunction "2_2") (pintype "passive"))
      (node (ref "U1") (pin "24") (pinfunction "GHA_24") (pintype "passive"))
    )
    (net (code "16") (name "/GHA-2") (class "Default")
      (node (ref "R10") (pin "2") (pinfunction "2_2") (pintype "passive"))
      (node (ref "U2") (pin "24") (pinfunction "GHA_24") (pintype "passive"))
    )
    (net (code "17") (name "/GHB-1") (class "Default")
      (node (ref "R5") (pin "2") (pinfunction "2_2") (pintype "passive"))
      (node (ref "U1") (pin "20") (pinfunction "GHB_20") (pintype "passive"))
    )
    (net (code "18") (name "/GHB-2") (class "Default")
      (node (ref "R14") (pin "2") (pinfunction "2_2") (pintype "passive"))
      (node (ref "U2") (pin "20") (pinfunction "GHB_20") (pintype "passive"))
    )
    (net (code "19") (name "/GLA-1") (class "Default")
      (node (ref "R4") (pin "1") (pinfunction "1_1") (pintype "passive"))
      (node (ref "U1") (pin "2") (pinfunction "GLA_2") (pintype "passive"))
    )
    (net (code "20") (name "/GLA-2") (class "Default")
      (node (ref "R13") (pin "1") (pinfunction "1_1") (pintype "passive"))
      (node (ref "U2") (pin "2") (pinfunction "GLA_2") (pintype "passive"))
    )
    (net (code "21") (name "/GLB-1") (class "Default")
      (node (ref "R6") (pin "1") (pinfunction "1_1") (pintype "passive"))
      (node (ref "U1") (pin "18") (pinfunction "GLB_18") (pintype "passive"))
    )
    (net (code "22") (name "/GLB-2") (class "Default")
      (node (ref "R15") (pin "1") (pinfunction "1_1") (pintype "passive"))
      (node (ref "U2") (pin "18") (pinfunction "GLB_18") (pintype "passive"))
    )
    (net (code "23") (name "/KEY-Down") (class "Default")
      (node (ref "U10") (pin "43") (pinfunction "PB7_43") (pintype "bidirectional"))
      (node (ref "U5") (pin "6") (pinfunction "D_6") (pintype "passive"))
    )
    (net (code "24") (name "/KEY-Left") (class "Default")
      (node (ref "U10") (pin "2") (pinfunction "PC13-TAMPER-RTC_2") (pintype "bidirectional"))
      (node (ref "U5") (pin "3") (pinfunction "L_3") (pintype "passive"))
    )
    (net (code "25") (name "/KEY-Mid") (class "Default")
      (node (ref "U10") (pin "46") (pinfunction "PB9_46") (pintype "bidirectional"))
      (node (ref "U5") (pin "2") (pinfunction "MID_2") (pintype "passive"))
    )
    (net (code "26") (name "/KEY-Right") (class "Default")
      (node (ref "U10") (pin "42") (pinfunction "PB6_42") (pintype "bidirectional"))
      (node (ref "U5") (pin "4") (pinfunction "R_4") (pintype "passive"))
    )
    (net (code "27") (name "/KEY-Up") (class "Default")
      (node (ref "U10") (pin "45") (pinfunction "PB8_45") (pintype "bidirectional"))
      (node (ref "U5") (pin "1") (pinfunction "U_1") (pintype "passive"))
    )
    (net (code "28") (name "/LED") (class "Default")
      (node (ref "LED4") (pin "C") (pinfunction "C_C") (pintype "passive"))
      (node (ref "U10") (pin "3") (pinfunction "PC14-OSC32_IN_3") (pintype "bidirectional"))
    )
    (net (code "29") (name "/MPU6050-SCL") (class "Default")
      (node (ref "P2") (pin "3") (pinfunction "3_3") (pintype "passive"))
      (node (ref "U10") (pin "19") (pinfunction "PB1_19") (pintype "bidirectional"))
    )
    (net (code "30") (name "/MPU6050-SDA") (class "Default")
      (node (ref "P2") (pin "4") (pinfunction "4_4") (pintype "passive"))
      (node (ref "U10") (pin "18") (pinfunction "PB0_18") (pintype "bidirectional"))
    )
    (net (code "31") (name "/Motor-1-A") (class "Default")
      (node (ref "R3") (pin "1") (pinfunction "1_1") (pintype "passive"))
      (node (ref "U1") (pin "8") (pinfunction "BLO_8") (pintype "passive"))
      (node (ref "U10") (pin "13") (pinfunction "PA3_13") (pintype "bidirectional"))
    )
    (net (code "32") (name "/Motor-1-B") (class "Default")
      (node (ref "R2") (pin "1") (pinfunction "1_1") (pintype "passive"))
      (node (ref "U1") (pin "10") (pinfunction "ALO_10") (pintype "passive"))
      (node (ref "U10") (pin "12") (pinfunction "PA2_12") (pintype "bidirectional"))
    )
    (net (code "33") (name "/Motor-2-A") (class "Default")
      (node (ref "R12") (pin "1") (pinfunction "1_1") (pintype "passive"))
      (node (ref "U10") (pin "11") (pinfunction "PA1_11") (pintype "bidirectional"))
      (node (ref "U2") (pin "8") (pinfunction "BLO_8") (pintype "passive"))
    )
    (net (code "34") (name "/Motor-2-B") (class "Default")
      (node (ref "R11") (pin "1") (pinfunction "1_1") (pintype "passive"))
      (node (ref "U10") (pin "10") (pinfunction "PA0-WKUP_10") (pintype "bidirectional"))
      (node (ref "U2") (pin "10") (pinfunction "ALO_10") (pintype "passive"))
    )
    (net (code "35") (name "/NRST") (class "Default")
      (node (ref "C50") (pin "2") (pinfunction "2_2") (pintype "passive"))
      (node (ref "R50") (pin "1") (pinfunction "1_1") (pintype "passive"))
      (node (ref "S50") (pin "2") (pinfunction "2_2") (pintype "passive"))
      (node (ref "U10") (pin "7") (pinfunction "NRST_7") (pintype "bidirectional"))
    )
    (net (code "36") (name "/OLED-D0") (class "Default")
      (node (ref "U10") (pin "39") (pinfunction "PB3/JTDO_39") (pintype "bidirectional"))
      (node (ref "U9") (pin "18") (pinfunction "D0_18") (pintype "passive"))
    )
    (net (code "37") (name "/OLED-D1") (class "Default")
      (node (ref "U10") (pin "38") (pinfunction "PA15/JTDI_38") (pintype "bidirectional"))
      (node (ref "U9") (pin "19") (pinfunction "D1_19") (pintype "passive"))
    )
    (net (code "38") (name "/OLED-DC") (class "Default")
      (node (ref "U10") (pin "40") (pinfunction "PB4/JNTRST_40") (pintype "bidirectional"))
      (node (ref "U9") (pin "15") (pinfunction "D/C#_15") (pintype "passive"))
    )
    (net (code "39") (name "/OLED-RST") (class "Default")
      (node (ref "U10") (pin "41") (pinfunction "PB5_41") (pintype "bidirectional"))
      (node (ref "U9") (pin "14") (pinfunction "RES#_14") (pintype "passive"))
    )
    (net (code "40") (name "/OSC-IN") (class "Default")
      (node (ref "C56") (pin "2") (pinfunction "2_2") (pintype "passive"))
      (node (ref "U10") (pin "5") (pinfunction "OSC_IN/PD0_5") (pintype "input"))
      (node (ref "Y5") (pin "1") (pinfunction "OSC2_1") (pintype "passive"))
    )
    (net (code "41") (name "/OSC-OUT") (class "Default")
      (node (ref "C57") (pin "2") (pinfunction "2_2") (pintype "passive"))
      (node (ref "U10") (pin "6") (pinfunction "OSC_OUT/PD1_6") (pintype "output"))
      (node (ref "Y5") (pin "3") (pinfunction "OSC1_3") (pintype "passive"))
    )
    (net (code "42") (name "/PA8-NO") (class "Default")
      (node (ref "P4") (pin "1") (pinfunction "1_1") (pintype "passive"))
      (node (ref "U10") (pin "29") (pinfunction "PA8_29") (pintype "bidirectional"))
    )
    (net (code "43") (name "/PA11-NO") (class "Default")
      (node (ref "U10") (pin "32") (pinfunction "PA11_32") (pintype "bidirectional+no_connect"))
    )
    (net (code "44") (name "/PA12--NO") (class "Default")
      (node (ref "U10") (pin "33") (pinfunction "PA12_33") (pintype "bidirectional+no_connect"))
    )
    (net (code "45") (name "/PB12-NO") (class "Default")
      (node (ref "P4") (pin "5") (pinfunction "5_5") (pintype "passive"))
      (node (ref "U10") (pin "25") (pinfunction "PB12_25") (pintype "bidirectional"))
    )
    (net (code "46") (name "/PB13-NO") (class "Default")
      (node (ref "P4") (pin "4") (pinfunction "4_4") (pintype "passive"))
      (node (ref "U10") (pin "26") (pinfunction "PB13_26") (pintype "bidirectional"))
    )
    (net (code "47") (name "/PB14-NO") (class "Default")
      (node (ref "P4") (pin "3") (pinfunction "3_3") (pintype "passive"))
      (node (ref "U10") (pin "27") (pinfunction "PB14_27") (pintype "bidirectional"))
    )
    (net (code "48") (name "/PB15-NO") (class "Default")
      (node (ref "P4") (pin "2") (pinfunction "2_2") (pintype "passive"))
      (node (ref "U10") (pin "28") (pinfunction "PB15_28") (pintype "bidirectional"))
    )
    (net (code "49") (name "/SA-1") (class "Default")
      (node (ref "B1") (pin "1") (pinfunction "+_1") (pintype "passive"))
      (node (ref "C4") (pin "2") (pinfunction "2_2") (pintype "passive"))
      (node (ref "Q1") (pin "3") (pinfunction "S_3") (pintype "passive"))
      (node (ref "Q2") (pin "2") (pinfunction "D_2") (pintype "passive"))
      (node (ref "U1") (pin "1") (pinfunction "SA_1") (pintype "passive"))
    )
    (net (code "50") (name "/SA-2") (class "Default")
      (node (ref "B2") (pin "1") (pinfunction "+_1") (pintype "passive"))
      (node (ref "C11") (pin "2") (pinfunction "2_2") (pintype "passive"))
      (node (ref "Q5") (pin "3") (pinfunction "S_3") (pintype "passive"))
      (node (ref "Q6") (pin "2") (pinfunction "D_2") (pintype "passive"))
      (node (ref "U2") (pin "1") (pinfunction "SA_1") (pintype "passive"))
    )
    (net (code "51") (name "/SB-1") (class "Default")
      (node (ref "B1") (pin "2") (pinfunction "-_2") (pintype "passive"))
      (node (ref "C7") (pin "2") (pinfunction "2_2") (pintype "passive"))
      (node (ref "Q3") (pin "3") (pinfunction "S_3") (pintype "passive"))
      (node (ref "Q4") (pin "2") (pinfunction "D_2") (pintype "passive"))
      (node (ref "U1") (pin "19") (pinfunction "SB_19") (pintype "passive"))
    )
    (net (code "52") (name "/SB-2") (class "Default")
      (node (ref "B2") (pin "2") (pinfunction "-_2") (pintype "passive"))
      (node (ref "C14") (pin "2") (pinfunction "2_2") (pintype "passive"))
      (node (ref "Q7") (pin "3") (pinfunction "S_3") (pintype "passive"))
      (node (ref "Q8") (pin "2") (pinfunction "D_2") (pintype "passive"))
      (node (ref "U2") (pin "19") (pinfunction "SB_19") (pintype "passive"))
    )
    (net (code "53") (name "/SWCLK") (class "Default")
      (node (ref "U10") (pin "37") (pinfunction "PA14/JTCK/SWCLK_37") (pintype "bidirectional"))
      (node (ref "USB2") (pin "2") (pinfunction "D-_2") (pintype "passive"))
    )
    (net (code "54") (name "/SWDIO") (class "Default")
      (node (ref "U10") (pin "34") (pinfunction "PA13/JTMS/SWDIO_34") (pintype "bidirectional"))
      (node (ref "USB2") (pin "3") (pinfunction "D+_3") (pintype "passive"))
    )
    (net (code "55") (name "/UART1-RX") (class "Default")
      (node (ref "U10") (pin "31") (pinfunction "PA10_31") (pintype "bidirectional"))
      (node (ref "USB1") (pin "2") (pinfunction "D-_2") (pintype "passive"))
    )
    (net (code "56") (name "/UART1-TX") (class "Default")
      (node (ref "U10") (pin "30") (pinfunction "PA9_30") (pintype "bidirectional"))
      (node (ref "USB1") (pin "3") (pinfunction "D+_3") (pintype "passive"))
    )
    (net (code "57") (name "12V") (class "Default")
      (node (ref "C1") (pin "2") (pinfunction "2_2") (pintype "passive"))
      (node (ref "C30") (pin "1") (pinfunction "1_1") (pintype "passive"))
      (node (ref "C31") (pin "1") (pinfunction "1_1") (pintype "passive"))
      (node (ref "C32") (pin "1") (pinfunction "1_1") (pintype "passive"))
      (node (ref "C8") (pin "2") (pinfunction "2_2") (pintype "passive"))
      (node (ref "D1") (pin "A") (pinfunction "A_A") (pintype "passive"))
      (node (ref "D2") (pin "A") (pinfunction "A_A") (pintype "passive"))
      (node (ref "Q1") (pin "2") (pinfunction "D_2") (pintype "passive"))
      (node (ref "Q3") (pin "2") (pinfunction "D_2") (pintype "passive"))
      (node (ref "Q5") (pin "2") (pinfunction "D_2") (pintype "passive"))
      (node (ref "Q7") (pin "2") (pinfunction "D_2") (pintype "passive"))
      (node (ref "R35") (pin "2") (pinfunction "2_2") (pintype "passive"))
      (node (ref "R41") (pin "2") (pinfunction "2_2") (pintype "passive"))
      (node (ref "S1") (pin "1") (pinfunction "1_1") (pintype "passive"))
      (node (ref "U30") (pin "2") (pinfunction "IN_2") (pintype "passive"))
    )
    (net (code "58") (name "A-3V3") (class "Default")
      (node (ref "C102") (pin "1") (pinfunction "1_1") (pintype "passive"))
      (node (ref "C13") (pin "1") (pinfunction "1_1") (pintype "passive"))
      (node (ref "C6") (pin "1") (pinfunction "1_1") (pintype "passive"))
      (node (ref "C64") (pin "1") (pintype "passive"))
      (node (ref "C65") (pin "1") (pintype "passive"))
      (node (ref "C66") (pin "1") (pintype "passive"))
      (node (ref "D101") (pin "2") (pinfunction "C_2") (pintype "passive"))
      (node (ref "P1") (pin "4") (pinfunction "4_4") (pintype "passive"))
      (node (ref "Q50") (pin "3") (pinfunction "E_3") (pintype "passive"))
      (node (ref "R18") (pin "1") (pinfunction "1_1") (pintype "passive"))
      (node (ref "R43") (pin "2") (pinfunction "2_2") (pintype "passive"))
      (node (ref "R44") (pin "2") (pinfunction "2_2") (pintype "passive"))
      (node (ref "R9") (pin "1") (pinfunction "1_1") (pintype "passive"))
      (node (ref "U1") (pin "11") (pinfunction "AHI_11") (pintype "passive"))
      (node (ref "U1") (pin "12") (pinfunction "VDD_12") (pintype "passive"))
      (node (ref "U1") (pin "9") (pinfunction "BHI_9") (pintype "passive"))
      (node (ref "U100") (pin "5") (pinfunction "OUT_5") (pintype "passive"))
      (node (ref "U100") (pin "6") (pinfunction "OUT_6") (pintype "passive"))
      (node (ref "U100") (pin "7") (pinfunction "FB#_7") (pintype "passive"))
      (node (ref "U2") (pin "11") (pinfunction "AHI_11") (pintype "passive"))
      (node (ref "U2") (pin "12") (pinfunction "VDD_12") (pintype "passive"))
      (node (ref "U2") (pin "9") (pinfunction "BHI_9") (pintype "passive"))
      (node (ref "U9") (pin "6") (pinfunction "VBAT_6") (pintype "passive"))
      (node (ref "U9") (pin "9") (pinfunction "VDD_9") (pintype "passive"))
    )
    (net (code "59") (name "A-5V") (class "Default")
      (node (ref "C36") (pin "2") (pinfunction "2_2") (pintype "passive"))
      (node (ref "C37") (pin "2") (pinfunction "2_2") (pintype "passive"))
      (node (ref "C38") (pin "1") (pinfunction "1_1") (pintype "passive"))
      (node (ref "C41") (pin "1") (pinfunction "1_1") (pintype "passive"))
      (node (ref "L30") (pin "2") (pinfunction "2_2") (pintype "passive"))
      (node (ref "R32") (pin "2") (pinfunction "2_2") (pintype "passive"))
      (node (ref "R42") (pin "2") (pinfunction "2_2") (pintype "passive"))
      (node (ref "U100") (pin "3") (pinfunction "IN_3") (pintype "passive"))
      (node (ref "U100") (pin "4") (pinfunction "IN_4") (pintype "passive"))
      (node (ref "U6") (pin "3") (pinfunction "IN_3") (pintype "passive"))
      (node (ref "U6") (pin "4") (pinfunction "IN_4") (pintype "passive"))
    )
    (net (code "60") (name "A-C-3V3") (class "Default")
      (node (ref "C39") (pin "1") (pinfunction "1_1") (pintype "passive"))
      (node (ref "C40") (pin "2") (pinfunction "2_2") (pintype "passive"))
      (node (ref "C51") (pin "2") (pinfunction "2_2") (pintype "passive"))
      (node (ref "C52") (pin "2") (pinfunction "2_2") (pintype "passive"))
      (node (ref "C53") (pin "2") (pinfunction "2_2") (pintype "passive"))
      (node (ref "C54") (pin "2") (pinfunction "2_2") (pintype "passive"))
      (node (ref "C55") (pin "2") (pinfunction "2_2") (pintype "passive"))
      (node (ref "D100") (pin "2") (pinfunction "C_2") (pintype "passive"))
      (node (ref "F4") (pin "1") (pinfunction "1_1") (pintype "passive"))
      (node (ref "P2") (pin "1") (pinfunction "1_1") (pintype "passive"))
      (node (ref "P3") (pin "1") (pinfunction "1_1") (pintype "passive"))
      (node (ref "R50") (pin "2") (pinfunction "2_2") (pintype "passive"))
      (node (ref "U10") (pin "1") (pinfunction "VBAT_1") (pintype "power_in"))
      (node (ref "U10") (pin "24") (pinfunction "VDD_1_24") (pintype "power_in"))
      (node (ref "U10") (pin "36") (pinfunction "VDD_2_36") (pintype "power_in"))
      (node (ref "U10") (pin "48") (pinfunction "VDD_3_48") (pintype "power_in"))
      (node (ref "U10") (pin "9") (pinfunction "VDDA_9") (pintype "power_in"))
    )
    (net (code "61") (name "A-GND") (class "Default")
      (node (ref "12V-IN") (pin "2") (pinfunction "GND_2") (pintype "passive"))
      (node (ref "C1") (pin "1") (pinfunction "1_1") (pintype "passive"))
      (node (ref "C10") (pin "1") (pinfunction "1_1") (pintype "passive"))
      (node (ref "C102") (pin "2") (pinfunction "2_2") (pintype "passive"))
      (node (ref "C12") (pin "1") (pinfunction "1_1") (pintype "passive"))
      (node (ref "C13") (pin "2") (pinfunction "2_2") (pintype "passive"))
      (node (ref "C3") (pin "1") (pinfunction "1_1") (pintype "passive"))
      (node (ref "C30") (pin "2") (pinfunction "2_2") (pintype "passive"))
      (node (ref "C31") (pin "2") (pinfunction "2_2") (pintype "passive"))
      (node (ref "C32") (pin "2") (pinfunction "2_2") (pintype "passive"))
      (node (ref "C34") (pin "2") (pinfunction "2_2") (pintype "passive"))
      (node (ref "C35") (pin "2") (pinfunction "2_2") (pintype "passive"))
      (node (ref "C36") (pin "1") (pinfunction "1_1") (pintype "passive"))
      (node (ref "C37") (pin "1") (pinfunction "1_1") (pintype "passive"))
      (node (ref "C41") (pin "2") (pinfunction "2_2") (pintype "passive"))
      (node (ref "C42") (pin "1") (pinfunction "1_1") (pintype "passive"))
      (node (ref "C43") (pin "1") (pinfunction "1_1") (pintype "passive"))
      (node (ref "C5") (pin "1") (pinfunction "1_1") (pintype "passive"))
      (node (ref "C6") (pin "2") (pinfunction "2_2") (pintype "passive"))
      (node (ref "C62") (pin "2") (pintype "passive"))
      (node (ref "C63") (pin "2") (pintype "passive"))
      (node (ref "C64") (pin "2") (pintype "passive"))
      (node (ref "C65") (pin "2") (pintype "passive"))
      (node (ref "C66") (pin "2") (pintype "passive"))
      (node (ref "C8") (pin "1") (pinfunction "1_1") (pintype "passive"))
      (node (ref "LED1") (pin "C") (pinfunction "C_C") (pintype "passive"))
      (node (ref "LED2") (pin "C") (pinfunction "C_C") (pintype "passive"))
      (node (ref "LED3") (pin "C") (pinfunction "C_C") (pintype "passive"))
      (node (ref "P1") (pin "3") (pinfunction "3_3") (pintype "passive"))
      (node (ref "Q2") (pin "3") (pinfunction "S_3") (pintype "passive"))
      (node (ref "Q4") (pin "3") (pinfunction "S_3") (pintype "passive"))
      (node (ref "Q6") (pin "3") (pinfunction "S_3") (pintype "passive"))
      (node (ref "Q8") (pin "3") (pinfunction "S_3") (pintype "passive"))
      (node (ref "R11") (pin "2") (pinfunction "2_2") (pintype "passive"))
      (node (ref "R12") (pin "2") (pinfunction "2_2") (pintype "passive"))
      (node (ref "R16") (pin "2") (pinfunction "2_2") (pintype "passive"))
      (node (ref "R2") (pin "2") (pinfunction "2_2") (pintype "passive"))
      (node (ref "R3") (pin "2") (pinfunction "2_2") (pintype "passive"))
      (node (ref "R33") (pin "1") (pinfunction "1_1") (pintype "passive"))
      (node (ref "R34") (pin "2") (pinfunction "2_2") (pintype "passive"))
      (node (ref "R37") (pin "1") (pinfunction "1_1") (pintype "passive"))
      (node (ref "R38") (pin "2") (pinfunction "2_2") (pintype "passive"))
      (node (ref "R60") (pin "1") (pinfunction "1_1") (pintype "passive"))
      (node (ref "R7") (pin "2") (pinfunction "2_2") (pintype "passive"))
      (node (ref "SPEAKER1") (pin "2") (pinfunction "-_2") (pintype "passive"))
      (node (ref "U1") (pin "13") (pinfunction "AGND_13") (pintype "passive"))
      (node (ref "U1") (pin "17") (pinfunction "GND_17") (pintype "passive"))
      (node (ref "U1") (pin "6") (pinfunction "GND_6") (pintype "passive"))
      (node (ref "U1") (pin "7") (pinfunction "GND_7") (pintype "passive"))
      (node (ref "U100") (pin "1") (pinfunction "GND_1") (pintype "passive"))
      (node (ref "U100") (pin "2") (pinfunction "~{EN}_2") (pintype "passive"))
      (node (ref "U2") (pin "13") (pinfunction "AGND_13") (pintype "passive"))
      (node (ref "U2") (pin "17") (pinfunction "GND_17") (pintype "passive"))
      (node (ref "U2") (pin "6") (pinfunction "GND_6") (pintype "passive"))
      (node (ref "U2") (pin "7") (pinfunction "GND_7") (pintype "passive"))
      (node (ref "U30") (pin "4") (pinfunction "GND_4") (pintype "passive"))
      (node (ref "U6") (pin "1") (pinfunction "GND_1") (pintype "passive"))
      (node (ref "U6") (pin "2") (pinfunction "~{EN}_2") (pintype "passive"))
      (node (ref "U9") (pin "1") (pinfunction "NC_1_1") (pintype "passive"))
      (node (ref "U9") (pin "10") (pinfunction "BS0_10") (pintype "passive"))
      (node (ref "U9") (pin "11") (pinfunction "BS1_11") (pintype "passive"))
      (node (ref "U9") (pin "12") (pinfunction "BS2_12") (pintype "passive"))
      (node (ref "U9") (pin "13") (pinfunction "CS#_13") (pintype "passive"))
      (node (ref "U9") (pin "16") (pinfunction "R/W#_16") (pintype "passive"))
      (node (ref "U9") (pin "17") (pinfunction "E/RD#_17") (pintype "passive"))
      (node (ref "U9") (pin "21") (pinfunction "D3_21") (pintype "passive"))
      (node (ref "U9") (pin "22") (pinfunction "D4_22") (pintype "passive"))
      (node (ref "U9") (pin "23") (pinfunction "D5_23") (pintype "passive"))
      (node (ref "U9") (pin "24") (pinfunction "D6_24") (pintype "passive"))
      (node (ref "U9") (pin "25") (pinfunction "D7_25") (pintype "passive"))
      (node (ref "U9") (pin "29") (pinfunction "VLSS_29") (pintype "passive"))
      (node (ref "U9") (pin "30") (pinfunction "NC_3_30") (pintype "passive"))
      (node (ref "U9") (pin "8") (pinfunction "VSS_8") (pintype "passive"))
      (node (ref "USB1") (pin "5") (pinfunction "GND_5") (pintype "passive"))
      (node (ref "USB2") (pin "5") (pinfunction "GND_5") (pintype "passive"))
    )
    (net (code "62") (name "D-GND") (class "Default")
      (node (ref "C39") (pin "2") (pinfunction "2_2") (pintype "passive"))
      (node (ref "C40") (pin "1") (pinfunction "1_1") (pintype "passive"))
      (node (ref "C50") (pin "1") (pinfunction "1_1") (pintype "passive"))
      (node (ref "C51") (pin "1") (pinfunction "1_1") (pintype "passive"))
      (node (ref "C52") (pin "1") (pinfunction "1_1") (pintype "passive"))
      (node (ref "C53") (pin "1") (pinfunction "1_1") (pintype "passive"))
      (node (ref "C54") (pin "1") (pinfunction "1_1") (pintype "passive"))
      (node (ref "C55") (pin "1") (pinfunction "1_1") (pintype "passive"))
      (node (ref "C56") (pin "1") (pinfunction "1_1") (pintype "passive"))
      (node (ref "C57") (pin "1") (pinfunction "1_1") (pintype "passive"))
      (node (ref "P2") (pin "2") (pinfunction "2_2") (pintype "passive"))
      (node (ref "P3") (pin "2") (pinfunction "2_2") (pintype "passive"))
      (node (ref "R38") (pin "1") (pinfunction "1_1") (pintype "passive"))
      (node (ref "R51") (pin "1") (pinfunction "1_1") (pintype "passive"))
      (node (ref "R551") (pin "1") (pinfunction "1_1") (pintype "passive"))
      (node (ref "S50") (pin "1") (pinfunction "1_1") (pintype "passive"))
      (node (ref "U10") (pin "23") (pinfunction "VSS_1_23") (pintype "power_in"))
      (node (ref "U10") (pin "35") (pinfunction "VSS_2_35") (pintype "power_in"))
      (node (ref "U10") (pin "47") (pinfunction "VSS_3_47") (pintype "power_in"))
      (node (ref "U10") (pin "8") (pinfunction "VSSA_8") (pintype "power_in"))
      (node (ref "U5") (pin "5") (pinfunction "COM_5") (pintype "passive"))
    )
    (net (code "63") (name "IN-3V3") (class "Default")
      (node (ref "D100") (pin "1") (pinfunction "A_1") (pintype "passive"))
      (node (ref "D101") (pin "1") (pinfunction "A_1") (pintype "passive"))
      (node (ref "USB1") (pin "1") (pinfunction "VBUS_1") (pintype "passive"))
      (node (ref "USB2") (pin "1") (pinfunction "VBUS_1") (pintype "passive"))
    )
    (net (code "64") (name "Net-(12V-IN-VCC)") (class "Default")
      (node (ref "12V-IN") (pin "1") (pinfunction "VCC_1") (pintype "passive"))
      (node (ref "S1") (pin "2") (pinfunction "2_2") (pintype "passive"))
    )
    (net (code "65") (name "Net-(C33-Pad2)") (class "Default")
      (node (ref "C33") (pin "2") (pinfunction "2_2") (pintype "passive"))
      (node (ref "R30") (pin "1") (pinfunction "1_1") (pintype "passive"))
    )
    (net (code "66") (name "Net-(C38-Pad2)") (class "Default")
      (node (ref "C38") (pin "2") (pinfunction "2_2") (pintype "passive"))
      (node (ref "R36") (pin "2") (pinfunction "2_2") (pintype "passive"))
    )
    (net (code "67") (name "Net-(LED1-PadA)") (class "Default")
      (node (ref "LED1") (pin "A") (pinfunction "A_A") (pintype "passive"))
      (node (ref "R41") (pin "1") (pinfunction "1_1") (pintype "passive"))
    )
    (net (code "68") (name "Net-(LED2-PadA)") (class "Default")
      (node (ref "LED2") (pin "A") (pinfunction "A_A") (pintype "passive"))
      (node (ref "R42") (pin "1") (pinfunction "1_1") (pintype "passive"))
    )
    (net (code "69") (name "Net-(LED3-PadA)") (class "Default")
      (node (ref "LED3") (pin "A") (pinfunction "A_A") (pintype "passive"))
      (node (ref "R43") (pin "1") (pinfunction "1_1") (pintype "passive"))
    )
    (net (code "70") (name "Net-(LED4-PadA)") (class "Default")
      (node (ref "LED4") (pin "A") (pinfunction "A_A") (pintype "passive"))
      (node (ref "R44") (pin "1") (pinfunction "1_1") (pintype "passive"))
    )
    (net (code "71") (name "Net-(Q1-G)") (class "Default")
      (node (ref "Q1") (pin "1") (pinfunction "G_1") (pintype "passive"))
      (node (ref "R1") (pin "1") (pinfunction "1_1") (pintype "passive"))
    )
    (net (code "72") (name "Net-(Q2-G)") (class "Default")
      (node (ref "Q2") (pin "1") (pinfunction "G_1") (pintype "passive"))
      (node (ref "R4") (pin "2") (pinfunction "2_2") (pintype "passive"))
    )
    (net (code "73") (name "Net-(Q3-G)") (class "Default")
      (node (ref "Q3") (pin "1") (pinfunction "G_1") (pintype "passive"))
      (node (ref "R5") (pin "1") (pinfunction "1_1") (pintype "passive"))
    )
    (net (code "74") (name "Net-(Q4-G)") (class "Default")
      (node (ref "Q4") (pin "1") (pinfunction "G_1") (pintype "passive"))
      (node (ref "R6") (pin "2") (pinfunction "2_2") (pintype "passive"))
    )
    (net (code "75") (name "Net-(Q5-G)") (class "Default")
      (node (ref "Q5") (pin "1") (pinfunction "G_1") (pintype "passive"))
      (node (ref "R10") (pin "1") (pinfunction "1_1") (pintype "passive"))
    )
    (net (code "76") (name "Net-(Q6-G)") (class "Default")
      (node (ref "Q6") (pin "1") (pinfunction "G_1") (pintype "passive"))
      (node (ref "R13") (pin "2") (pinfunction "2_2") (pintype "passive"))
    )
    (net (code "77") (name "Net-(Q7-G)") (class "Default")
      (node (ref "Q7") (pin "1") (pinfunction "G_1") (pintype "passive"))
      (node (ref "R14") (pin "1") (pinfunction "1_1") (pintype "passive"))
    )
    (net (code "78") (name "Net-(Q8-G)") (class "Default")
      (node (ref "Q8") (pin "1") (pinfunction "G_1") (pintype "passive"))
      (node (ref "R15") (pin "2") (pinfunction "2_2") (pintype "passive"))
    )
    (net (code "79") (name "Net-(Q50-B)") (class "Default")
      (node (ref "Q50") (pin "1") (pinfunction "B_1") (pintype "passive"))
      (node (ref "SPEAKER1") (pin "1") (pinfunction "+_1") (pintype "passive"))
    )
    (net (code "80") (name "Net-(Q50-C)") (class "Default")
      (node (ref "Q50") (pin "2") (pinfunction "C_2") (pintype "passive"))
      (node (ref "R53") (pin "2") (pinfunction "2_2") (pintype "passive"))
    )
    (net (code "81") (name "Net-(R31-Pad1)") (class "Default")
      (node (ref "R31") (pin "1") (pinfunction "1_1") (pintype "passive"))
      (node (ref "R32") (pin "1") (pinfunction "1_1") (pintype "passive"))
      (node (ref "R34") (pin "1") (pinfunction "1_1") (pintype "passive"))
      (node (ref "R36") (pin "1") (pinfunction "1_1") (pintype "passive"))
    )
    (net (code "82") (name "Net-(U1-CP1)") (class "Default")
      (node (ref "C2") (pin "2") (pinfunction "2_2") (pintype "passive"))
      (node (ref "U1") (pin "5") (pinfunction "CP1_5") (pintype "passive"))
    )
    (net (code "83") (name "Net-(U1-CP2)") (class "Default")
      (node (ref "C2") (pin "1") (pinfunction "1_1") (pintype "passive"))
      (node (ref "U1") (pin "4") (pinfunction "CP2_4") (pintype "passive"))
    )
    (net (code "84") (name "Net-(U1-FAULT)") (class "Default")
      (node (ref "R9") (pin "2") (pinfunction "2_2") (pintype "passive"))
      (node (ref "U1") (pin "15") (pinfunction "FAULT_15") (pintype "passive"))
    )
    (net (code "85") (name "Net-(U1-RDEAD)") (class "Default")
      (node (ref "R7") (pin "1") (pinfunction "1_1") (pintype "passive"))
      (node (ref "U1") (pin "14") (pinfunction "RDEAD_14") (pintype "passive"))
    )
    (net (code "86") (name "Net-(U1-RESET)") (class "Default")
      (node (ref "R8") (pin "1") (pinfunction "1_1") (pintype "passive"))
      (node (ref "U1") (pin "16") (pinfunction "RESET_16") (pintype "passive"))
    )
    (net (code "87") (name "Net-(U1-VREG)") (class "Default")
      (node (ref "C5") (pin "2") (pinfunction "2_2") (pintype "passive"))
      (node (ref "U1") (pin "22") (pinfunction "VREG_22") (pintype "passive"))
    )
    (net (code "88") (name "Net-(U2-CP1)") (class "Default")
      (node (ref "C9") (pin "2") (pinfunction "2_2") (pintype "passive"))
      (node (ref "U2") (pin "5") (pinfunction "CP1_5") (pintype "passive"))
    )
    (net (code "89") (name "Net-(U2-CP2)") (class "Default")
      (node (ref "C9") (pin "1") (pinfunction "1_1") (pintype "passive"))
      (node (ref "U2") (pin "4") (pinfunction "CP2_4") (pintype "passive"))
    )
    (net (code "90") (name "Net-(U2-FAULT)") (class "Default")
      (node (ref "R18") (pin "2") (pinfunction "2_2") (pintype "passive"))
      (node (ref "U2") (pin "15") (pinfunction "FAULT_15") (pintype "passive"))
    )
    (net (code "91") (name "Net-(U2-RDEAD)") (class "Default")
      (node (ref "R16") (pin "1") (pinfunction "1_1") (pintype "passive"))
      (node (ref "U2") (pin "14") (pinfunction "RDEAD_14") (pintype "passive"))
    )
    (net (code "92") (name "Net-(U2-RESET)") (class "Default")
      (node (ref "R17") (pin "1") (pinfunction "1_1") (pintype "passive"))
      (node (ref "U2") (pin "16") (pinfunction "RESET_16") (pintype "passive"))
    )
    (net (code "93") (name "Net-(U2-VREG)") (class "Default")
      (node (ref "C12") (pin "2") (pinfunction "2_2") (pintype "passive"))
      (node (ref "U2") (pin "22") (pinfunction "VREG_22") (pintype "passive"))
    )
    (net (code "94") (name "Net-(U6-FB#)") (class "Default")
      (node (ref "C42") (pin "2") (pinfunction "2_2") (pintype "passive"))
      (node (ref "C43") (pin "2") (pinfunction "2_2") (pintype "passive"))
      (node (ref "F4") (pin "2") (pinfunction "2_2") (pintype "passive"))
      (node (ref "U6") (pin "5") (pinfunction "OUT_5") (pintype "passive"))
      (node (ref "U6") (pin "6") (pinfunction "OUT_6") (pintype "passive"))
      (node (ref "U6") (pin "7") (pinfunction "FB#_7") (pintype "passive"))
    )
    (net (code "95") (name "Net-(U9-C1N)") (class "Default")
      (node (ref "C61") (pin "2") (pintype "passive"))
      (node (ref "U9") (pin "5") (pinfunction "C1N_5") (pintype "passive"))
    )
    (net (code "96") (name "Net-(U9-C1P)") (class "Default")
      (node (ref "C61") (pin "1") (pintype "passive"))
      (node (ref "U9") (pin "4") (pinfunction "C1P_4") (pintype "passive"))
    )
    (net (code "97") (name "Net-(U9-C2N)") (class "Default")
      (node (ref "C60") (pin "2") (pintype "passive"))
      (node (ref "U9") (pin "3") (pinfunction "C2N_3") (pintype "passive"))
    )
    (net (code "98") (name "Net-(U9-C2P)") (class "Default")
      (node (ref "C60") (pin "1") (pintype "passive"))
      (node (ref "U9") (pin "2") (pinfunction "C2P_2") (pintype "passive"))
    )
    (net (code "99") (name "Net-(U9-IREF)") (class "Default")
      (node (ref "R60") (pin "2") (pinfunction "2_2") (pintype "passive"))
      (node (ref "U9") (pin "26") (pinfunction "IREF_26") (pintype "passive"))
    )
    (net (code "100") (name "Net-(U9-VCC)") (class "Default")
      (node (ref "C63") (pin "1") (pintype "passive"))
      (node (ref "U9") (pin "28") (pinfunction "VCC_28") (pintype "passive"))
    )
    (net (code "101") (name "Net-(U9-VCOMH)") (class "Default")
      (node (ref "C62") (pin "1") (pintype "passive"))
      (node (ref "U9") (pin "27") (pinfunction "VCOMH_27") (pintype "passive"))
    )
    (net (code "102") (name "Net-(U30-AAM)") (class "Default")
      (node (ref "C35") (pin "1") (pinfunction "1_1") (pintype "passive"))
      (node (ref "R33") (pin "2") (pinfunction "2_2") (pintype "passive"))
      (node (ref "U30") (pin "1") (pinfunction "AAM_1") (pintype "passive"))
    )
    (net (code "103") (name "Net-(U30-BST)") (class "Default")
      (node (ref "R30") (pin "2") (pinfunction "2_2") (pintype "passive"))
      (node (ref "U30") (pin "5") (pinfunction "BST_5") (pintype "passive"))
    )
    (net (code "104") (name "Net-(U30-EN)") (class "Default")
      (node (ref "R35") (pin "1") (pinfunction "1_1") (pintype "passive"))
      (node (ref "R37") (pin "2") (pinfunction "2_2") (pintype "passive"))
      (node (ref "U30") (pin "6") (pinfunction "EN_6") (pintype "passive"))
    )
    (net (code "105") (name "Net-(U30-FB)") (class "Default")
      (node (ref "R31") (pin "2") (pinfunction "2_2") (pintype "passive"))
      (node (ref "U30") (pin "8") (pinfunction "FB_8") (pintype "passive"))
    )
    (net (code "106") (name "Net-(U30-SW)") (class "Default")
      (node (ref "C33") (pin "1") (pinfunction "1_1") (pintype "passive"))
      (node (ref "L30") (pin "1") (pinfunction "1_1") (pintype "passive"))
      (node (ref "U30") (pin "3") (pinfunction "SW_3") (pintype "passive"))
    )
    (net (code "107") (name "Net-(U30-VCC)") (class "Default")
      (node (ref "C34") (pin "1") (pinfunction "1_1") (pintype "passive"))
      (node (ref "U30") (pin "7") (pinfunction "VCC_7") (pintype "passive"))
    )
    (net (code "108") (name "VBB-1") (class "Default")
      (node (ref "C3") (pin "2") (pinfunction "2_2") (pintype "passive"))
      (node (ref "D1") (pin "K") (pinfunction "K_K") (pintype "passive"))
      (node (ref "R8") (pin "2") (pinfunction "2_2") (pintype "passive"))
      (node (ref "U1") (pin "3") (pinfunction "VBB_3") (pintype "passive"))
    )
    (net (code "109") (name "VBB-2") (class "Default")
      (node (ref "C10") (pin "2") (pinfunction "2_2") (pintype "passive"))
      (node (ref "D2") (pin "K") (pinfunction "K_K") (pintype "passive"))
      (node (ref "R17") (pin "2") (pinfunction "2_2") (pintype "passive"))
      (node (ref "U2") (pin "3") (pinfunction "VBB_3") (pintype "passive"))
    )
    (net (code "110") (name "unconnected-(S1-Pad3)") (class "Default")
      (node (ref "S1") (pin "3") (pinfunction "3_3") (pintype "passive+no_connect"))
    )
    (net (code "111") (name "unconnected-(U6-~{RST}-Pad8)") (class "Default")
      (node (ref "U6") (pin "8") (pinfunction "~{RST}_8") (pintype "passive"))
    )
    (net (code "112") (name "unconnected-(U9-D2-Pad20)") (class "Default")
      (node (ref "U9") (pin "20") (pinfunction "D2_20") (pintype "passive+no_connect"))
    )
    (net (code "113") (name "unconnected-(U9-NC_2-Pad7)") (class "Default")
      (node (ref "U9") (pin "7") (pinfunction "NC_2_7") (pintype "passive+no_connect"))
    )
    (net (code "114") (name "unconnected-(U100-~{RST}-Pad8)") (class "Default")
      (node (ref "U100") (pin "8") (pinfunction "~{RST}_8") (pintype "passive"))
    )
    (net (code "115") (name "unconnected-(USB1-GND-Pad6)") (class "Default")
      (node (ref "USB1") (pin "6") (pinfunction "GND_6") (pintype "passive"))
    )
    (net (code "116") (name "unconnected-(USB1-GND-Pad7)") (class "Default")
      (node (ref "USB1") (pin "7") (pinfunction "GND_7") (pintype "passive"))
    )
    (net (code "117") (name "unconnected-(USB1-GND-Pad8)") (class "Default")
      (node (ref "USB1") (pin "8") (pinfunction "GND_8") (pintype "passive"))
    )
    (net (code "118") (name "unconnected-(USB1-GND-Pad9)") (class "Default")
      (node (ref "USB1") (pin "9") (pinfunction "GND_9") (pintype "passive"))
    )
    (net (code "119") (name "unconnected-(USB1-ID-Pad4)") (class "Default")
      (node (ref "USB1") (pin "4") (pinfunction "ID_4") (pintype "passive+no_connect"))
    )
    (net (code "120") (name "unconnected-(USB2-GND-Pad6)") (class "Default")
      (node (ref "USB2") (pin "6") (pinfunction "GND_6") (pintype "passive"))
    )
    (net (code "121") (name "unconnected-(USB2-GND-Pad7)") (class "Default")
      (node (ref "USB2") (pin "7") (pinfunction "GND_7") (pintype "passive"))
    )
    (net (code "122") (name "unconnected-(USB2-GND-Pad8)") (class "Default")
      (node (ref "USB2") (pin "8") (pinfunction "GND_8") (pintype "passive"))
    )
    (net (code "123") (name "unconnected-(USB2-GND-Pad9)") (class "Default")
      (node (ref "USB2") (pin "9") (pinfunction "GND_9") (pintype "passive"))
    )
    (net (code "124") (name "unconnected-(USB2-ID-Pad4)") (class "Default")
      (node (ref "USB2") (pin "4") (pinfunction "ID_4") (pintype "passive+no_connect"))
    )
  )
)
